# SX70_Flash_Tester_MINI.net
KiCad netlist of a schematic drawn in EAGLE
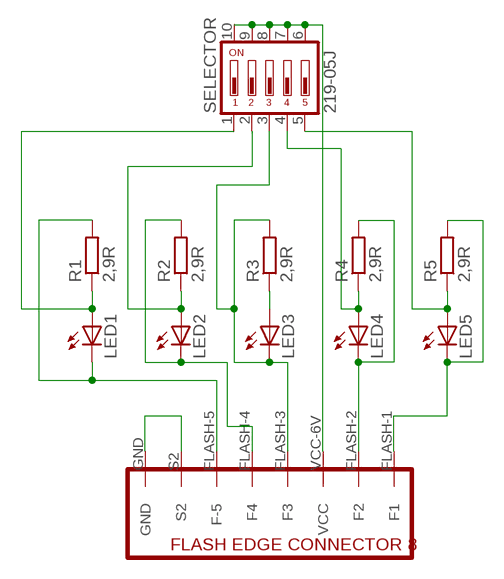
[diagram p0: schematic, sheet 1]

(export (version "E")
  (design (tool "Eeschema 10.0.6"))
  (components
    (comp (ref "FLASH_TESTER")
      (value "SX70-FLASH-EDGE8-MALE")
      (footprint "eagle-import:SX70-FLASH-EDGE8")
      (libsource (lib "eagle-import") (part "SX70-FLASH-EDGE8-MALE"))
    )
    (comp (ref "LED1")
      (value "LEDCHIPLED_0805")
      (footprint "eagle-import:CHIPLED_0805")
      (libsource (lib "eagle-import") (part "LEDCHIPLED_0805"))
    )
    (comp (ref "LED2")
      (value "LEDCHIPLED_0805")
      (footprint "eagle-import:CHIPLED_0805")
      (libsource (lib "eagle-import") (part "LEDCHIPLED_0805"))
    )
    (comp (ref "LED3")
      (value "LEDCHIPLED_0805")
      (footprint "eagle-import:CHIPLED_0805")
      (libsource (lib "eagle-import") (part "LEDCHIPLED_0805"))
    )
    (comp (ref "LED4")
      (value "LEDCHIPLED_0805")
      (footprint "eagle-import:CHIPLED_0805")
      (libsource (lib "eagle-import") (part "LEDCHIPLED_0805"))
    )
    (comp (ref "LED5")
      (value "LEDCHIPLED_0805")
      (footprint "eagle-import:CHIPLED_0805")
      (libsource (lib "eagle-import") (part "LEDCHIPLED_0805"))
    )
    (comp (ref "R1")
      (value "2,9R")
      (footprint "eagle-import:M0805")
      (libsource (lib "eagle-import") (part "R-EU_M0805"))
    )
    (comp (ref "R2")
      (value "2,9R")
      (footprint "eagle-import:M0805")
      (libsource (lib "eagle-import") (part "R-EU_M0805"))
    )
    (comp (ref "R3")
      (value "2,9R")
      (footprint "eagle-import:M0805")
      (libsource (lib "eagle-import") (part "R-EU_M0805"))
    )
    (comp (ref "R4")
      (value "2,9R")
      (footprint "eagle-import:M0805")
      (libsource (lib "eagle-import") (part "R-EU_M0805"))
    )
    (comp (ref "R5")
      (value "2,9R")
      (footprint "eagle-import:M0805")
      (libsource (lib "eagle-import") (part "R-EU_M0805"))
    )
    (comp (ref "SELECTOR")
      (value "219-05J")
      (footprint "eagle-import:CTS-219-05J")
      (libsource (lib "eagle-import") (part "219-05J"))
    )
  )
  (nets
    (net (code "1") (name "Net-(FLASH_TESTER-F-5)") (class "Default")
      (node (ref "FLASH_TESTER") (pin "FLASH-5") (pinfunction "F-5_FLASH-5") (pintype "bidirectional"))
      (node (ref "LED1") (pin "C") (pinfunction "C_C") (pintype "passive"))
      (node (ref "R1") (pin "2") (pinfunction "2_2") (pintype "passive"))
    )
    (net (code "2") (name "Net-(FLASH_TESTER-F1)") (class "Default")
      (node (ref "FLASH_TESTER") (pin "FLASH-1") (pinfunction "F1_FLASH-1") (pintype "bidirectional"))
      (node (ref "LED5") (pin "C") (pinfunction "C_C") (pintype "passive"))
      (node (ref "R5") (pin "2") (pinfunction "2_2") (pintype "passive"))
    )
    (net (code "3") (name "Net-(FLASH_TESTER-F2)") (class "Default")
      (node (ref "FLASH_TESTER") (pin "FLASH-2") (pinfunction "F2_FLASH-2") (pintype "bidirectional"))
      (node (ref "LED4") (pin "C") (pinfunction "C_C") (pintype "passive"))
      (node (ref "R4") (pin "2") (pinfunction "2_2") (pintype "passive"))
    )
    (net (code "4") (name "Net-(FLASH_TESTER-F3)") (class "Default")
      (node (ref "FLASH_TESTER") (pin "FLASH-3") (pinfunction "F3_FLASH-3") (pintype "bidirectional"))
      (node (ref "LED3") (pin "C") (pinfunction "C_C") (pintype "passive"))
      (node (ref "R3") (pin "2") (pinfunction "2_2") (pintype "passive"))
      (node (ref "SELECTOR") (pin "3") (pinfunction "3_3") (pintype "passive"))
    )
    (net (code "5") (name "Net-(FLASH_TESTER-F4)") (class "Default")
      (node (ref "FLASH_TESTER") (pin "FLASH-4") (pinfunction "F4_FLASH-4") (pintype "bidirectional"))
      (node (ref "LED2") (pin "C") (pinfunction "C_C") (pintype "passive"))
      (node (ref "R2") (pin "2") (pinfunction "2_2") (pintype "passive"))
    )
    (net (code "6") (name "Net-(FLASH_TESTER-PadGND)") (class "Default")
      (node (ref "FLASH_TESTER") (pin "GND") (pinfunction "GND_GND") (pintype "bidirectional"))
      (node (ref "FLASH_TESTER") (pin "S2") (pinfunction "S2_S2") (pintype "bidirectional"))
    )
    (net (code "7") (name "Net-(FLASH_TESTER-VCC)") (class "Default")
      (node (ref "FLASH_TESTER") (pin "VCC-6V") (pinfunction "VCC_VCC-6V") (pintype "bidirectional"))
      (node (ref "SELECTOR") (pin "10") (pinfunction "10_10") (pintype "passive"))
      (node (ref "SELECTOR") (pin "6") (pinfunction "6_6") (pintype "passive"))
      (node (ref "SELECTOR") (pin "7") (pinfunction "7_7") (pintype "passive"))
      (node (ref "SELECTOR") (pin "8") (pinfunction "8_8") (pintype "passive"))
      (node (ref "SELECTOR") (pin "9") (pinfunction "9_9") (pintype "passive"))
    )
    (net (code "8") (name "Net-(LED1-PadA)") (class "Default")
      (node (ref "LED1") (pin "A") (pinfunction "A_A") (pintype "passive"))
      (node (ref "R1") (pin "1") (pinfunction "1_1") (pintype "passive"))
      (node (ref "SELECTOR") (pin "1") (pinfunction "1_1") (pintype "passive"))
    )
    (net (code "9") (name "Net-(LED2-PadA)") (class "Default")
      (node (ref "LED2") (pin "A") (pinfunction "A_A") (pintype "passive"))
      (node (ref "R2") (pin "1") (pinfunction "1_1") (pintype "passive"))
      (node (ref "SELECTOR") (pin "2") (pinfunction "2_2") (pintype "passive"))
    )
    (net (code "10") (name "Net-(LED3-PadA)") (class "Default")
      (node (ref "LED3") (pin "A") (pinfunction "A_A") (pintype "passive"))
      (node (ref "R3") (pin "1") (pinfunction "1_1") (pintype "passive"))
    )
    (net (code "11") (name "Net-(LED4-PadA)") (class "Default")
      (node (ref "LED4") (pin "A") (pinfunction "A_A") (pintype "passive"))
      (node (ref "R4") (pin "1") (pinfunction "1_1") (pintype "passive"))
      (node (ref "SELECTOR") (pin "4") (pinfunction "4_4") (pintype "passive"))
    )
    (net (code "12") (name "Net-(LED5-PadA)") (class "Default")
      (node (ref "LED5") (pin "A") (pinfunction "A_A") (pintype "passive"))
      (node (ref "R5") (pin "1") (pinfunction "1_1") (pintype "passive"))
      (node (ref "SELECTOR") (pin "5") (pinfunction "5_5") (pintype "passive"))
    )
  )
)
